# motherboard.net
KiCad netlist of a schematic drawn in Altium Designer
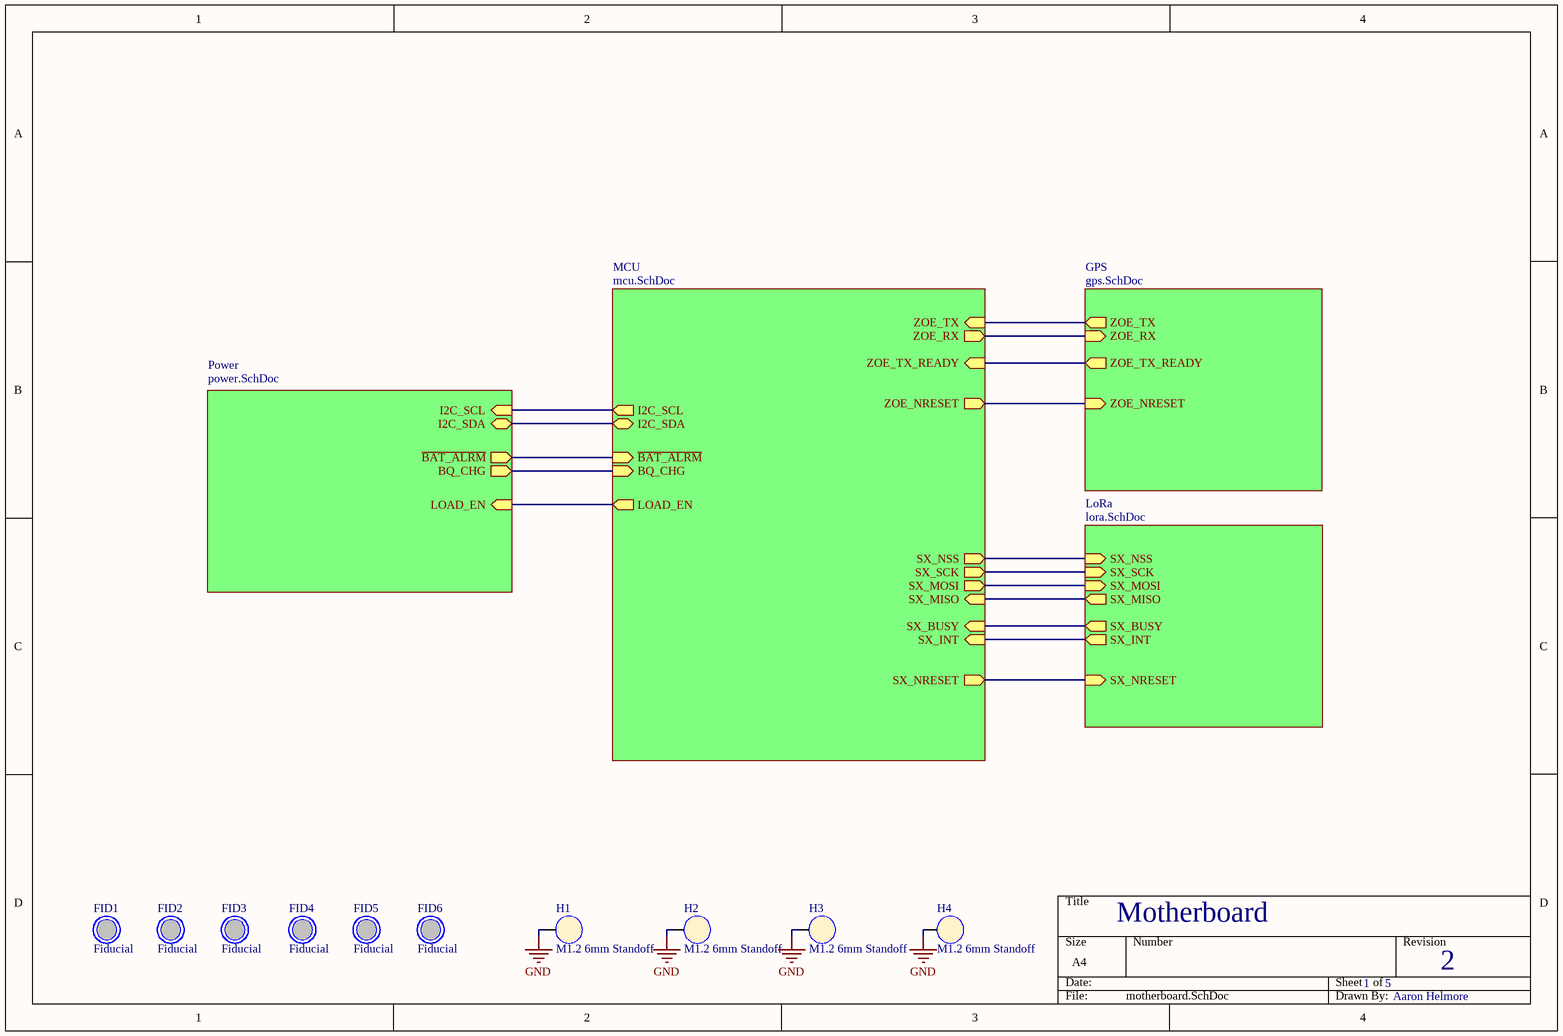
[diagram p0: motherboard.SchDoc]

(export (version "E")
  (design (tool "Eeschema 10.0.6"))
  (components
    (comp (ref "FID1")
      (value "Fiducial")
      (footprint "FIDUCIAL_0.5MM_SOLDER_1MM_MASK")
      (libsource (lib "thesis_schem_lib") (part "Fiducial"))
    )
    (comp (ref "FID2")
      (value "Fiducial")
      (footprint "FIDUCIAL_0.5MM_SOLDER_1MM_MASK")
      (libsource (lib "thesis_schem_lib") (part "Fiducial"))
    )
    (comp (ref "FID3")
      (value "Fiducial")
      (footprint "FIDUCIAL_0.5MM_SOLDER_1MM_MASK")
      (libsource (lib "thesis_schem_lib") (part "Fiducial"))
    )
    (comp (ref "FID4")
      (value "Fiducial")
      (footprint "FIDUCIAL_0.5MM_SOLDER_1MM_MASK")
      (libsource (lib "thesis_schem_lib") (part "Fiducial"))
    )
    (comp (ref "FID5")
      (value "Fiducial")
      (footprint "FIDUCIAL_0.5MM_SOLDER_1MM_MASK")
      (libsource (lib "thesis_schem_lib") (part "Fiducial"))
    )
    (comp (ref "FID6")
      (value "Fiducial")
      (footprint "FIDUCIAL_0.5MM_SOLDER_1MM_MASK")
      (libsource (lib "thesis_schem_lib") (part "Fiducial"))
    )
    (comp (ref "H1")
      (value "M1.2 6mm Standoff")
      (footprint "M1.2_6mm_STANDOFF")
      (libsource (lib "thesis_schem_lib") (part "M1.2 6mm Standoff"))
    )
    (comp (ref "H2")
      (value "M1.2 6mm Standoff")
      (footprint "M1.2_6mm_STANDOFF")
      (libsource (lib "thesis_schem_lib") (part "M1.2 6mm Standoff"))
    )
    (comp (ref "H3")
      (value "M1.2 6mm Standoff")
      (footprint "M1.2_6mm_STANDOFF")
      (libsource (lib "thesis_schem_lib") (part "M1.2 6mm Standoff"))
    )
    (comp (ref "H4")
      (value "M1.2 6mm Standoff")
      (footprint "M1.2_6mm_STANDOFF")
      (libsource (lib "thesis_schem_lib") (part "M1.2 6mm Standoff"))
    )
  )
  (nets
    (net (code "17") (name "GND") (class "Default")
      (node (ref "H1") (pin "1") (pinfunction "VCC_1") (pintype "passive"))
      (node (ref "H2") (pin "1") (pinfunction "VCC_1") (pintype "passive"))
      (node (ref "H3") (pin "1") (pinfunction "VCC_1") (pintype "passive"))
      (node (ref "H4") (pin "1") (pinfunction "VCC_1") (pintype "passive"))
    )
  )
)
